# 2_Micro_USB_B.net
KiCad netlist of a schematic drawn in Altium Designer
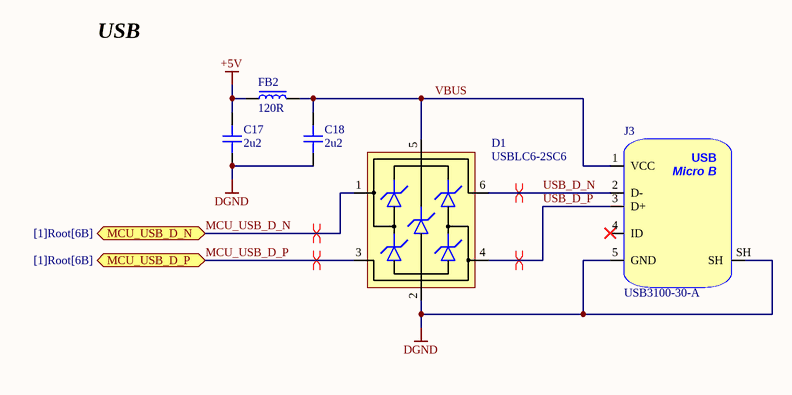
[diagram p0: [2]Micro_USB_B.SchDoc]

(export (version "E")
  (design (tool "Eeschema 10.0.6"))
  (components
    (comp (ref "C17")
      (value "2u2")
      (footprint "CAP_0603")
      (description "16V")
      (libsource (lib "Schematic-Lib-PhilsLab") (part "CAP_0603"))
    )
    (comp (ref "C18")
      (value "2u2")
      (footprint "CAP_0603")
      (description "16V")
      (libsource (lib "Schematic-Lib-PhilsLab") (part "CAP_0603"))
    )
    (comp (ref "D1")
      (value "USBLC6-2SC6")
      (footprint "SOT-23-6")
      (description "Low-Capacitance ESD Protection USB")
      (fields (field (name "MANUFACTURER") "STMicroelectronics"))
      (libsource (lib "Schematic-Lib-PhilsLab") (part "USBLC6-2SC6"))
    )
    (comp (ref "FB2")
      (value "120R")
      (footprint "FB_0603")
      (description "30mOhm")
      (libsource (lib "Schematic-Lib-PhilsLab") (part "FB_0603"))
    )
    (comp (ref "J3")
      (value "USB3100-30-A")
      (footprint "USB3100-30-A")
      (description "USB Connector Type Micro B 2.0 SMD Reverse Mount")
      (fields (field (name "MANUFACTURER") "GCT"))
      (libsource (lib "Schematic-Lib-PhilsLab") (part "USB3100-30-A"))
    )
  )
  (nets
    (net (code "1") (name "+5V") (class "Default")
      (node (ref "C17") (pin "2") (pinfunction "2_2") (pintype "passive"))
      (node (ref "FB2") (pin "1") (pinfunction "1_1") (pintype "passive"))
    )
    (net (code "2") (name "/MCU_USB_D_N") (class "Default")
      (node (ref "D1") (pin "1") (pinfunction "IO1_1") (pintype "bidirectional"))
    )
    (net (code "3") (name "/MCU_USB_D_P") (class "Default")
      (node (ref "D1") (pin "3") (pinfunction "IO2_3") (pintype "bidirectional"))
    )
    (net (code "4") (name "/USB_D_N") (class "Default")
      (node (ref "D1") (pin "6") (pinfunction "IO1_6") (pintype "bidirectional"))
      (node (ref "J3") (pin "2") (pinfunction "D-_2") (pintype "passive"))
    )
    (net (code "5") (name "/USB_D_P") (class "Default")
      (node (ref "D1") (pin "4") (pinfunction "IO2_4") (pintype "bidirectional"))
      (node (ref "J3") (pin "3") (pinfunction "D+_3") (pintype "passive"))
    )
    (net (code "6") (name "/VBUS") (class "Default")
      (node (ref "C18") (pin "2") (pinfunction "2_2") (pintype "passive"))
      (node (ref "D1") (pin "5") (pinfunction "VBUS_5") (pintype "power_in"))
      (node (ref "FB2") (pin "2") (pinfunction "2_2") (pintype "passive"))
      (node (ref "J3") (pin "1") (pinfunction "VCC_1") (pintype "passive"))
    )
    (net (code "7") (name "DGND") (class "Default")
      (node (ref "C17") (pin "1") (pinfunction "1_1") (pintype "passive"))
      (node (ref "C18") (pin "1") (pinfunction "1_1") (pintype "passive"))
      (node (ref "D1") (pin "2") (pinfunction "GND_2") (pintype "power_in"))
      (node (ref "J3") (pin "5") (pinfunction "GND_5") (pintype "passive"))
      (node (ref "J3") (pin "SH") (pinfunction "SH_SH") (pintype "passive"))
    )
    (net (code "8") (name "unconnected-(J3-ID-Pad4)") (class "Default")
      (node (ref "J3") (pin "4") (pinfunction "ID_4") (pintype "passive+no_connect"))
    )
  )
)
